# XBee-Regulated.net
KiCad netlist of a schematic drawn in EAGLE
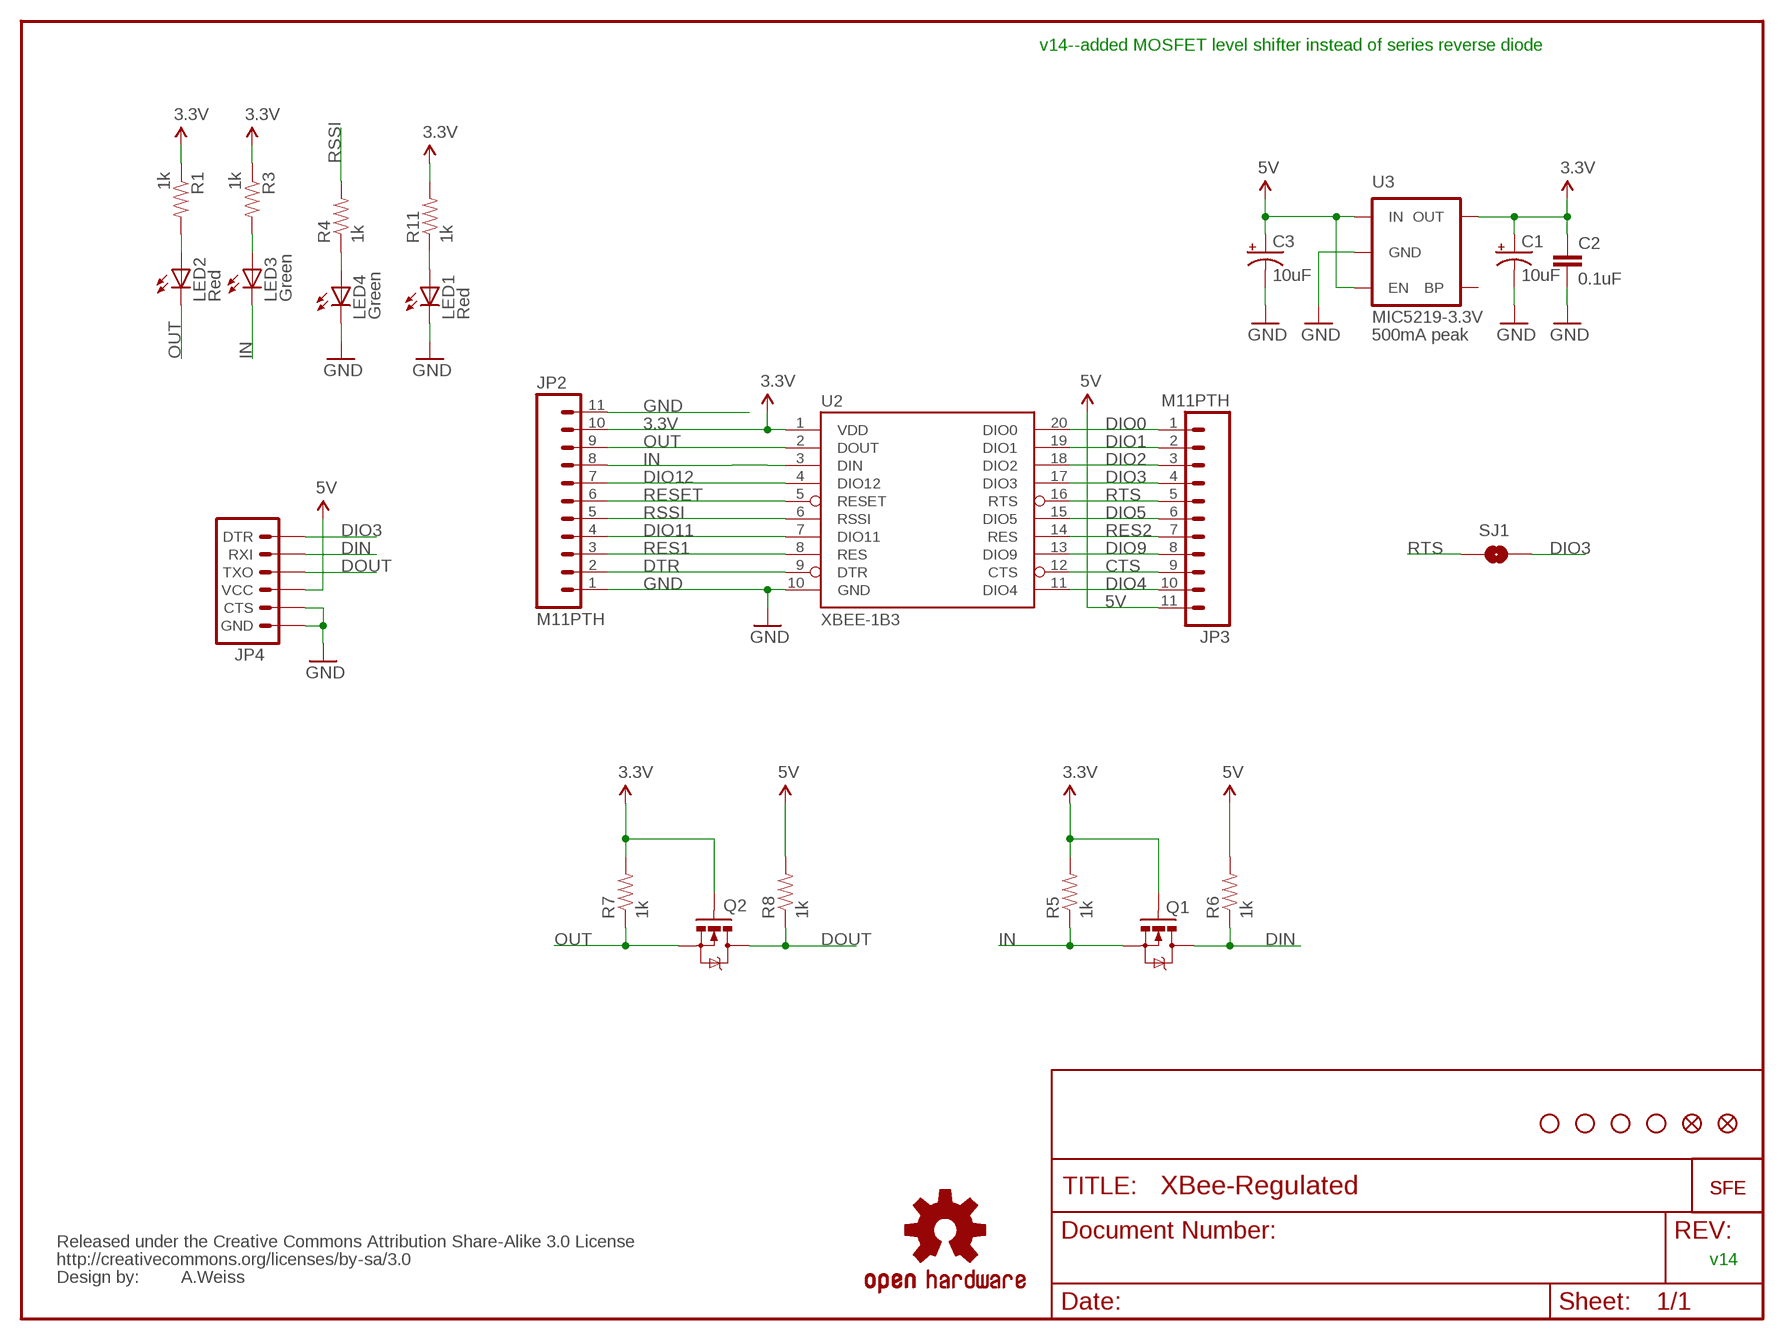
[diagram p0: schematic, sheet 1]

(export (version "E")
  (design (tool "Eeschema 10.0.6"))
  (components
    (comp (ref "C1")
      (value "10uF")
      (footprint "eagle-import:EIA3216")
      (libsource (lib "eagle-import") (part "CAP_POL1206"))
    )
    (comp (ref "C2")
      (value "0.1uF")
      (footprint "eagle-import:0402-CAP")
      (libsource (lib "eagle-import") (part "CAP0402-CAP"))
    )
    (comp (ref "C3")
      (value "10uF")
      (footprint "eagle-import:EIA3216")
      (libsource (lib "eagle-import") (part "CAP_POL1206"))
    )
    (comp (ref "JP2")
      (value "M11PTH")
      (footprint "eagle-import:1X11")
      (libsource (lib "eagle-import") (part "M11PTH"))
    )
    (comp (ref "JP3")
      (value "M11PTH")
      (footprint "eagle-import:1X11")
      (libsource (lib "eagle-import") (part "M11PTH"))
    )
    (comp (ref "JP4")
      (value "ARDUINO_SERIAL_PROGRAMPTH")
      (footprint "eagle-import:1X06")
      (libsource (lib "eagle-import") (part "ARDUINO_SERIAL_PROGRAMPTH"))
    )
    (comp (ref "LED1")
      (value "Red")
      (footprint "eagle-import:LED-0603")
      (libsource (lib "eagle-import") (part "LED0603"))
    )
    (comp (ref "LED2")
      (value "Red")
      (footprint "eagle-import:LED-0603")
      (libsource (lib "eagle-import") (part "LED0603"))
    )
    (comp (ref "LED3")
      (value "Green")
      (footprint "eagle-import:LED-0603")
      (libsource (lib "eagle-import") (part "LED0603"))
    )
    (comp (ref "LED4")
      (value "Green")
      (footprint "eagle-import:LED-0603")
      (libsource (lib "eagle-import") (part "LED0603"))
    )
    (comp (ref "Q1")
      (value "MOSFET-NCHANNELSMD")
      (footprint "eagle-import:SOT23-3")
      (libsource (lib "eagle-import") (part "MOSFET-NCHANNELSMD"))
    )
    (comp (ref "Q2")
      (value "MOSFET-NCHANNELSMD")
      (footprint "eagle-import:SOT23-3")
      (libsource (lib "eagle-import") (part "MOSFET-NCHANNELSMD"))
    )
    (comp (ref "R1")
      (value "1k")
      (footprint "eagle-import:0402-RES")
      (libsource (lib "eagle-import") (part "RESISTOR0402-RES"))
    )
    (comp (ref "R3")
      (value "1k")
      (footprint "eagle-import:0402-RES")
      (libsource (lib "eagle-import") (part "RESISTOR0402-RES"))
    )
    (comp (ref "R4")
      (value "1k")
      (footprint "eagle-import:0402-RES")
      (libsource (lib "eagle-import") (part "RESISTOR0402-RES"))
    )
    (comp (ref "R5")
      (value "1k")
      (footprint "eagle-import:0402-RES")
      (libsource (lib "eagle-import") (part "RESISTOR0402-RES"))
    )
    (comp (ref "R6")
      (value "1k")
      (footprint "eagle-import:0402-RES")
      (libsource (lib "eagle-import") (part "RESISTOR0402-RES"))
    )
    (comp (ref "R7")
      (value "1k")
      (footprint "eagle-import:0402-RES")
      (libsource (lib "eagle-import") (part "RESISTOR0402-RES"))
    )
    (comp (ref "R8")
      (value "1k")
      (footprint "eagle-import:0402-RES")
      (libsource (lib "eagle-import") (part "RESISTOR0402-RES"))
    )
    (comp (ref "R11")
      (value "1k")
      (footprint "eagle-import:0402-RES")
      (libsource (lib "eagle-import") (part "RESISTOR0402-RES"))
    )
    (comp (ref "SJ1")
      (value "SOLDERJUMPERNO")
      (footprint "eagle-import:SJ_2S-NO")
      (libsource (lib "eagle-import") (part "SOLDERJUMPERNO"))
    )
    (comp (ref "U$1")
      (value "LOGO-SFESK")
      (footprint "eagle-import:SFE-LOGO-FLAME")
      (libsource (lib "eagle-import") (part "LOGO-SFESK"))
    )
    (comp (ref "U$3")
      (value "OSHW-LOGOS")
      (footprint "eagle-import:OSHW-LOGO-S")
      (libsource (lib "eagle-import") (part "OSHW-LOGOS"))
    )
    (comp (ref "U$4")
      (value "LOGO-SFENEW")
      (footprint "eagle-import:SFE-NEW-WEBLOGO")
      (libsource (lib "eagle-import") (part "LOGO-SFENEW"))
    )
    (comp (ref "U$5")
      (value "STAND-OFF")
      (footprint "eagle-import:STAND-OFF")
      (libsource (lib "eagle-import") (part "STAND-OFF"))
    )
    (comp (ref "U$7")
      (value "FIDUCIAL1X2")
      (footprint "eagle-import:FIDUCIAL-1X2")
      (libsource (lib "eagle-import") (part "FIDUCIAL1X2"))
    )
    (comp (ref "U$8")
      (value "CREATIVE_COMMONS")
      (footprint "eagle-import:CREATIVE_COMMONS")
      (libsource (lib "eagle-import") (part "CREATIVE_COMMONS"))
    )
    (comp (ref "U$9")
      (value "STAND-OFF")
      (footprint "eagle-import:STAND-OFF")
      (libsource (lib "eagle-import") (part "STAND-OFF"))
    )
    (comp (ref "U$10")
      (value "STAND-OFF")
      (footprint "eagle-import:STAND-OFF")
      (libsource (lib "eagle-import") (part "STAND-OFF"))
    )
    (comp (ref "U$11")
      (value "STAND-OFF")
      (footprint "eagle-import:STAND-OFF")
      (libsource (lib "eagle-import") (part "STAND-OFF"))
    )
    (comp (ref "U$16")
      (value "FIDUCIAL1X2")
      (footprint "eagle-import:FIDUCIAL-1X2")
      (libsource (lib "eagle-import") (part "FIDUCIAL1X2"))
    )
    (comp (ref "U2")
      (value "XBEE-1B3")
      (footprint "eagle-import:XBEE-SMD")
      (libsource (lib "eagle-import") (part "XBEE-1B3"))
    )
    (comp (ref "U3")
      (value "V_REG_LDOSMD")
      (footprint "eagle-import:SOT23-5")
      (libsource (lib "eagle-import") (part "V_REG_LDOSMD"))
    )
  )
  (nets
    (net (code "1") (name "/CTS") (class "Default")
      (node (ref "JP3") (pin "9") (pinfunction "9_9") (pintype "passive"))
      (node (ref "U2") (pin "12") (pinfunction "CTS_12") (pintype "output"))
    )
    (net (code "2") (name "/DIN") (class "Default")
      (node (ref "JP4") (pin "2") (pinfunction "RXI_2") (pintype "passive"))
      (node (ref "Q1") (pin "3") (pinfunction "D_3") (pintype "passive"))
      (node (ref "R6") (pin "1") (pinfunction "1_1") (pintype "passive"))
    )
    (net (code "3") (name "/DIO0") (class "Default")
      (node (ref "JP3") (pin "1") (pinfunction "1_1") (pintype "passive"))
      (node (ref "U2") (pin "20") (pinfunction "DIO0_20") (pintype "bidirectional"))
    )
    (net (code "4") (name "/DIO1") (class "Default")
      (node (ref "JP3") (pin "2") (pinfunction "2_2") (pintype "passive"))
      (node (ref "U2") (pin "19") (pinfunction "DIO1_19") (pintype "bidirectional"))
    )
    (net (code "5") (name "/DIO2") (class "Default")
      (node (ref "JP3") (pin "3") (pinfunction "3_3") (pintype "passive"))
      (node (ref "U2") (pin "18") (pinfunction "DIO2_18") (pintype "bidirectional"))
    )
    (net (code "6") (name "/DIO3") (class "Default")
      (node (ref "JP3") (pin "4") (pinfunction "4_4") (pintype "passive"))
      (node (ref "JP4") (pin "1") (pinfunction "DTR_1") (pintype "passive"))
      (node (ref "SJ1") (pin "2") (pinfunction "2_2") (pintype "passive"))
      (node (ref "U2") (pin "17") (pinfunction "DIO3_17") (pintype "bidirectional"))
    )
    (net (code "7") (name "/DIO4") (class "Default")
      (node (ref "JP3") (pin "10") (pinfunction "10_10") (pintype "passive"))
      (node (ref "U2") (pin "11") (pinfunction "DIO4_11") (pintype "bidirectional"))
    )
    (net (code "8") (name "/DIO5") (class "Default")
      (node (ref "JP3") (pin "6") (pinfunction "6_6") (pintype "passive"))
      (node (ref "U2") (pin "15") (pinfunction "DIO5_15") (pintype "bidirectional"))
    )
    (net (code "9") (name "/DIO9") (class "Default")
      (node (ref "JP3") (pin "8") (pinfunction "8_8") (pintype "passive"))
      (node (ref "U2") (pin "13") (pinfunction "DIO9_13") (pintype "bidirectional"))
    )
    (net (code "10") (name "/DIO11") (class "Default")
      (node (ref "JP2") (pin "4") (pinfunction "4_4") (pintype "passive"))
      (node (ref "U2") (pin "7") (pinfunction "DIO11_7") (pintype "bidirectional"))
    )
    (net (code "11") (name "/DIO12") (class "Default")
      (node (ref "JP2") (pin "7") (pinfunction "7_7") (pintype "passive"))
      (node (ref "U2") (pin "4") (pinfunction "DIO12_4") (pintype "bidirectional"))
    )
    (net (code "12") (name "/DOUT") (class "Default")
      (node (ref "JP4") (pin "3") (pinfunction "TXO_3") (pintype "passive"))
      (node (ref "Q2") (pin "3") (pinfunction "D_3") (pintype "passive"))
      (node (ref "R8") (pin "1") (pinfunction "1_1") (pintype "passive"))
    )
    (net (code "13") (name "/DTR") (class "Default")
      (node (ref "JP2") (pin "2") (pinfunction "2_2") (pintype "passive"))
      (node (ref "U2") (pin "9") (pinfunction "DTR_9") (pintype "bidirectional"))
    )
    (net (code "14") (name "/IN") (class "Default")
      (node (ref "JP2") (pin "8") (pinfunction "8_8") (pintype "passive"))
      (node (ref "LED3") (pin "C") (pinfunction "C_C") (pintype "passive"))
      (node (ref "Q1") (pin "2") (pinfunction "S_2") (pintype "passive"))
      (node (ref "R5") (pin "1") (pinfunction "1_1") (pintype "passive"))
      (node (ref "U2") (pin "3") (pinfunction "DIN_3") (pintype "input"))
    )
    (net (code "15") (name "/OUT") (class "Default")
      (node (ref "JP2") (pin "9") (pinfunction "9_9") (pintype "passive"))
      (node (ref "LED2") (pin "C") (pinfunction "C_C") (pintype "passive"))
      (node (ref "Q2") (pin "2") (pinfunction "S_2") (pintype "passive"))
      (node (ref "R7") (pin "1") (pinfunction "1_1") (pintype "passive"))
      (node (ref "U2") (pin "2") (pinfunction "DOUT_2") (pintype "output"))
    )
    (net (code "16") (name "/RES1") (class "Default")
      (node (ref "JP2") (pin "3") (pinfunction "3_3") (pintype "passive"))
      (node (ref "U2") (pin "8") (pinfunction "RES_8") (pintype "bidirectional"))
    )
    (net (code "17") (name "/RES2") (class "Default")
      (node (ref "JP3") (pin "7") (pinfunction "7_7") (pintype "passive"))
      (node (ref "U2") (pin "14") (pinfunction "RES_14") (pintype "bidirectional"))
    )
    (net (code "18") (name "/RESET") (class "Default")
      (node (ref "JP2") (pin "6") (pinfunction "6_6") (pintype "passive"))
      (node (ref "U2") (pin "5") (pinfunction "RESET_5") (pintype "input"))
    )
    (net (code "19") (name "/RSSI") (class "Default")
      (node (ref "JP2") (pin "5") (pinfunction "5_5") (pintype "passive"))
      (node (ref "R4") (pin "2") (pinfunction "2_2") (pintype "passive"))
      (node (ref "U2") (pin "6") (pinfunction "RSSI_6") (pintype "bidirectional"))
    )
    (net (code "20") (name "/RTS") (class "Default")
      (node (ref "JP3") (pin "5") (pinfunction "5_5") (pintype "passive"))
      (node (ref "SJ1") (pin "1") (pinfunction "1_1") (pintype "passive"))
      (node (ref "U2") (pin "16") (pinfunction "RTS_16") (pintype "input"))
    )
    (net (code "21") (name "3.3V") (class "Default")
      (node (ref "C1") (pin "A") (pinfunction "+_A") (pintype "passive"))
      (node (ref "C2") (pin "1") (pinfunction "1_1") (pintype "passive"))
      (node (ref "JP2") (pin "10") (pinfunction "10_10") (pintype "passive"))
      (node (ref "Q1") (pin "1") (pinfunction "G_1") (pintype "passive"))
      (node (ref "Q2") (pin "1") (pinfunction "G_1") (pintype "passive"))
      (node (ref "R1") (pin "1") (pinfunction "1_1") (pintype "passive"))
      (node (ref "R11") (pin "2") (pinfunction "2_2") (pintype "passive"))
      (node (ref "R3") (pin "1") (pinfunction "1_1") (pintype "passive"))
      (node (ref "R5") (pin "2") (pinfunction "2_2") (pintype "passive"))
      (node (ref "R7") (pin "2") (pinfunction "2_2") (pintype "passive"))
      (node (ref "U2") (pin "1") (pinfunction "VDD_1") (pintype "power_in"))
      (node (ref "U3") (pin "5") (pinfunction "OUT_5") (pintype "passive"))
    )
    (net (code "22") (name "5V") (class "Default")
      (node (ref "C3") (pin "A") (pinfunction "+_A") (pintype "passive"))
      (node (ref "JP3") (pin "11") (pinfunction "11_11") (pintype "passive"))
      (node (ref "JP4") (pin "4") (pinfunction "VCC_4") (pintype "passive"))
      (node (ref "R6") (pin "2") (pinfunction "2_2") (pintype "passive"))
      (node (ref "R8") (pin "2") (pinfunction "2_2") (pintype "passive"))
      (node (ref "U3") (pin "1") (pinfunction "IN_1") (pintype "input"))
      (node (ref "U3") (pin "3") (pinfunction "EN_3") (pintype "input"))
    )
    (net (code "23") (name "GND") (class "Default")
      (node (ref "C1") (pin "C") (pinfunction "-_C") (pintype "passive"))
      (node (ref "C2") (pin "2") (pinfunction "2_2") (pintype "passive"))
      (node (ref "C3") (pin "C") (pinfunction "-_C") (pintype "passive"))
      (node (ref "JP2") (pin "1") (pinfunction "1_1") (pintype "passive"))
      (node (ref "JP2") (pin "11") (pinfunction "11_11") (pintype "passive"))
      (node (ref "JP4") (pin "5") (pinfunction "CTS_5") (pintype "passive"))
      (node (ref "JP4") (pin "6") (pinfunction "GND_6") (pintype "passive"))
      (node (ref "LED1") (pin "C") (pinfunction "C_C") (pintype "passive"))
      (node (ref "LED4") (pin "C") (pinfunction "C_C") (pintype "passive"))
      (node (ref "U2") (pin "10") (pinfunction "GND_10") (pintype "power_in"))
      (node (ref "U3") (pin "2") (pinfunction "GND_2") (pintype "input"))
    )
    (net (code "24") (name "Net-(LED1-PadA)") (class "Default")
      (node (ref "LED1") (pin "A") (pinfunction "A_A") (pintype "passive"))
      (node (ref "R11") (pin "1") (pinfunction "1_1") (pintype "passive"))
    )
    (net (code "25") (name "Net-(LED2-PadA)") (class "Default")
      (node (ref "LED2") (pin "A") (pinfunction "A_A") (pintype "passive"))
      (node (ref "R1") (pin "2") (pinfunction "2_2") (pintype "passive"))
    )
    (net (code "26") (name "Net-(LED3-PadA)") (class "Default")
      (node (ref "LED3") (pin "A") (pinfunction "A_A") (pintype "passive"))
      (node (ref "R3") (pin "2") (pinfunction "2_2") (pintype "passive"))
    )
    (net (code "27") (name "Net-(LED4-PadA)") (class "Default")
      (node (ref "LED4") (pin "A") (pinfunction "A_A") (pintype "passive"))
      (node (ref "R4") (pin "1") (pinfunction "1_1") (pintype "passive"))
    )
    (net (code "28") (name "unconnected-(U3-BP-Pad4)") (class "Default")
      (node (ref "U3") (pin "4") (pinfunction "BP_4") (pintype "input"))
    )
  )
)
